# progressled.net
KiCad netlist of a schematic drawn in Altium Designer
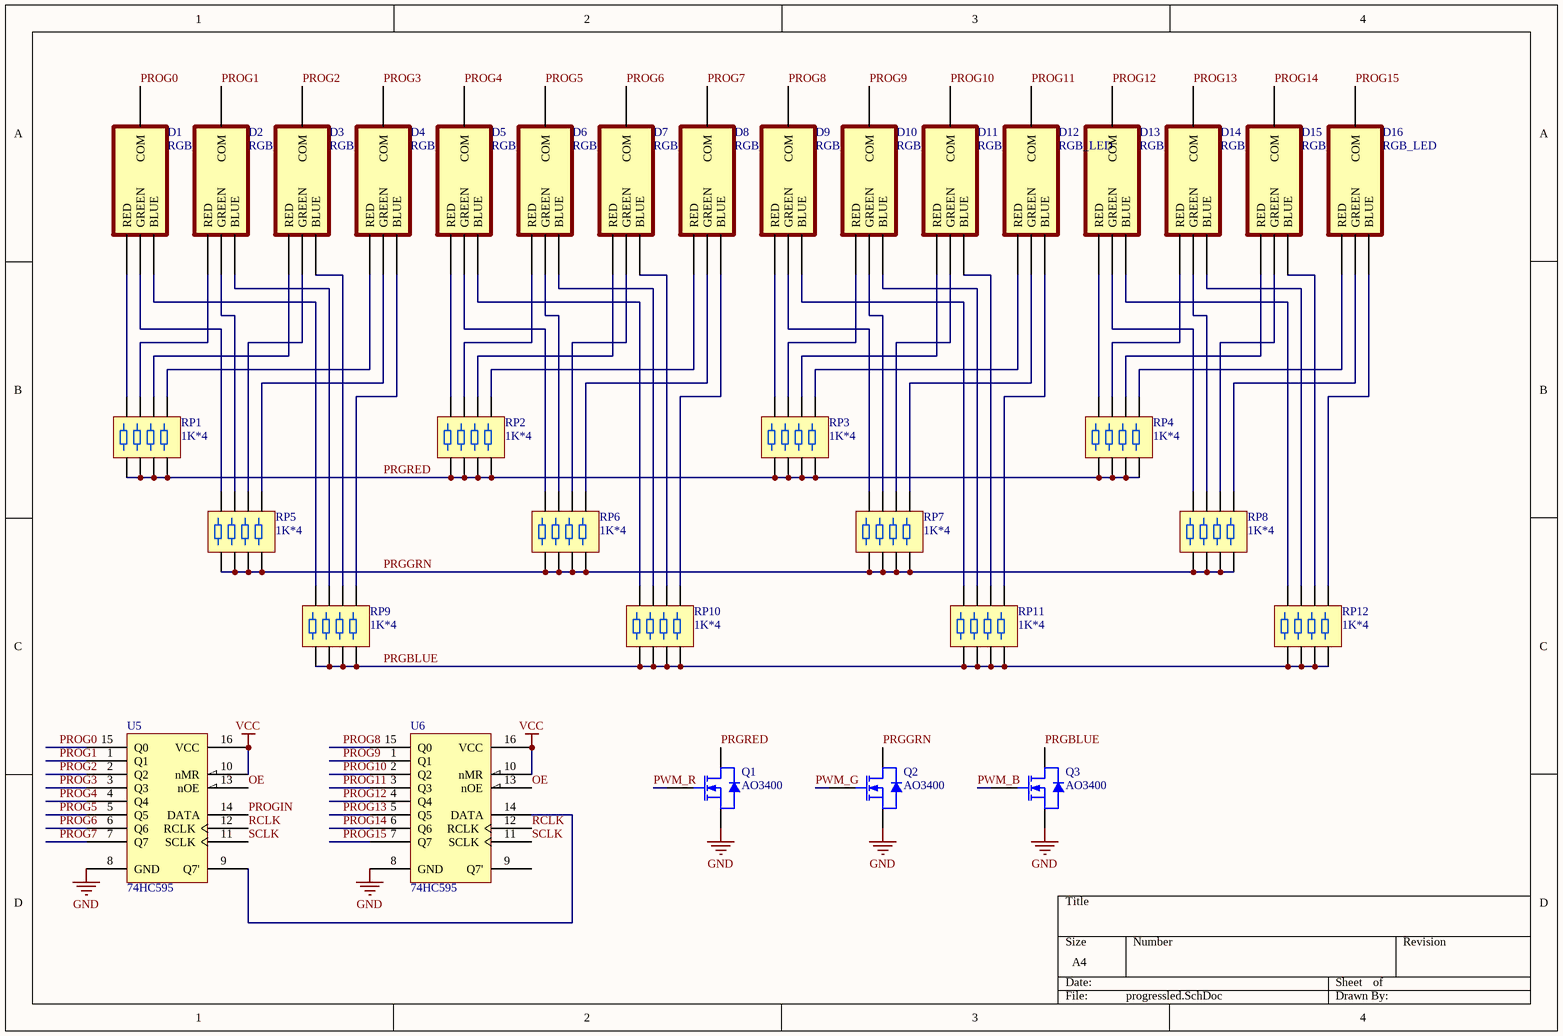
[diagram p0: progressled.SchDoc]

(export (version "E")
  (design (tool "Eeschema 10.0.6"))
  (components
    (comp (ref "D1")
      (value "RGB_LED")
      (footprint "0805_RGB")
      (libsource (lib "ntw_oldschlib") (part "RGBLED"))
    )
    (comp (ref "D2")
      (value "RGB_LED")
      (footprint "0805_RGB")
      (libsource (lib "ntw_oldschlib") (part "RGBLED"))
    )
    (comp (ref "D3")
      (value "RGB_LED")
      (footprint "0805_RGB")
      (libsource (lib "ntw_oldschlib") (part "RGBLED"))
    )
    (comp (ref "D4")
      (value "RGB_LED")
      (footprint "0805_RGB")
      (libsource (lib "ntw_oldschlib") (part "RGBLED"))
    )
    (comp (ref "D5")
      (value "RGB_LED")
      (footprint "0805_RGB")
      (libsource (lib "ntw_oldschlib") (part "RGBLED"))
    )
    (comp (ref "D6")
      (value "RGB_LED")
      (footprint "0805_RGB")
      (libsource (lib "ntw_oldschlib") (part "RGBLED"))
    )
    (comp (ref "D7")
      (value "RGB_LED")
      (footprint "0805_RGB")
      (libsource (lib "ntw_oldschlib") (part "RGBLED"))
    )
    (comp (ref "D8")
      (value "RGB_LED")
      (footprint "0805_RGB")
      (libsource (lib "ntw_oldschlib") (part "RGBLED"))
    )
    (comp (ref "D9")
      (value "RGB_LED")
      (footprint "0805_RGB")
      (libsource (lib "ntw_oldschlib") (part "RGBLED"))
    )
    (comp (ref "D10")
      (value "RGB_LED")
      (footprint "0805_RGB")
      (libsource (lib "ntw_oldschlib") (part "RGBLED"))
    )
    (comp (ref "D11")
      (value "RGB_LED")
      (footprint "0805_RGB")
      (libsource (lib "ntw_oldschlib") (part "RGBLED"))
    )
    (comp (ref "D12")
      (value "RGB_LED")
      (footprint "0805_RGB")
      (libsource (lib "ntw_oldschlib") (part "RGBLED"))
    )
    (comp (ref "D13")
      (value "RGB_LED")
      (footprint "0805_RGB")
      (libsource (lib "ntw_oldschlib") (part "RGBLED"))
    )
    (comp (ref "D14")
      (value "RGB_LED")
      (footprint "0805_RGB")
      (libsource (lib "ntw_oldschlib") (part "RGBLED"))
    )
    (comp (ref "D15")
      (value "RGB_LED")
      (footprint "0805_RGB")
      (libsource (lib "ntw_oldschlib") (part "RGBLED"))
    )
    (comp (ref "D16")
      (value "RGB_LED")
      (footprint "0805_RGB")
      (libsource (lib "ntw_oldschlib") (part "RGBLED"))
    )
    (comp (ref "Q1")
      (value "AO3400")
      (footprint "SOT-23")
      (description "N-Channel MOSFET")
      (fields (field (name "PUBLISHER") "Altium Limited"))
      (libsource (lib "ntw_oldschlib") (part "AO3400"))
    )
    (comp (ref "Q2")
      (value "AO3400")
      (footprint "SOT-23")
      (description "N-Channel MOSFET")
      (fields (field (name "PUBLISHER") "Altium Limited"))
      (libsource (lib "ntw_oldschlib") (part "AO3400"))
    )
    (comp (ref "Q3")
      (value "AO3400")
      (footprint "SOT-23")
      (description "N-Channel MOSFET")
      (fields (field (name "PUBLISHER") "Altium Limited"))
      (libsource (lib "ntw_oldschlib") (part "AO3400"))
    )
    (comp (ref "RP1") (value "1K*4") (footprint "0603x4") (libsource (lib "ntw_oldschlib") (part "RPack_4")))
    (comp (ref "RP2") (value "1K*4") (footprint "0603x4") (libsource (lib "ntw_oldschlib") (part "RPack_4")))
    (comp (ref "RP3") (value "1K*4") (footprint "0603x4") (libsource (lib "ntw_oldschlib") (part "RPack_4")))
    (comp (ref "RP4") (value "1K*4") (footprint "0603x4") (libsource (lib "ntw_oldschlib") (part "RPack_4")))
    (comp (ref "RP5") (value "1K*4") (footprint "0603x4") (libsource (lib "ntw_oldschlib") (part "RPack_4")))
    (comp (ref "RP6") (value "1K*4") (footprint "0603x4") (libsource (lib "ntw_oldschlib") (part "RPack_4")))
    (comp (ref "RP7") (value "1K*4") (footprint "0603x4") (libsource (lib "ntw_oldschlib") (part "RPack_4")))
    (comp (ref "RP8") (value "1K*4") (footprint "0603x4") (libsource (lib "ntw_oldschlib") (part "RPack_4")))
    (comp (ref "RP9") (value "1K*4") (footprint "0603x4") (libsource (lib "ntw_oldschlib") (part "RPack_4")))
    (comp (ref "RP10") (value "1K*4") (footprint "0603x4") (libsource (lib "ntw_oldschlib") (part "RPack_4")))
    (comp (ref "RP11") (value "1K*4") (footprint "0603x4") (libsource (lib "ntw_oldschlib") (part "RPack_4")))
    (comp (ref "RP12") (value "1K*4") (footprint "0603x4") (libsource (lib "ntw_oldschlib") (part "RPack_4")))
    (comp (ref "U5")
      (value "74HC595")
      (footprint "TSSOP16")
      (description "8-bit serial-in, serial or parallel-out shift register with output latches; 3-state")
      (libsource (lib "ntw_oldschlib") (part "74HC595"))
    )
    (comp (ref "U6")
      (value "74HC595")
      (footprint "TSSOP16")
      (description "8-bit serial-in, serial or parallel-out shift register with output latches; 3-state")
      (libsource (lib "ntw_oldschlib") (part "74HC595"))
    )
  )
  (nets
    (net (code "1") (name "/OE") (class "Default")
      (node (ref "U5") (pin "13") (pinfunction "nOE_13") (pintype "passive"))
      (node (ref "U6") (pin "13") (pinfunction "nOE_13") (pintype "passive"))
    )
    (net (code "2") (name "/PRGBLUE") (class "Default")
      (node (ref "Q3") (pin "3") (pinfunction "D_3") (pintype "passive"))
      (node (ref "RP10") (pin "1") (pinfunction "1_1") (pintype "passive"))
      (node (ref "RP10") (pin "2") (pinfunction "2_2") (pintype "passive"))
      (node (ref "RP10") (pin "3") (pinfunction "3_3") (pintype "passive"))
      (node (ref "RP10") (pin "4") (pinfunction "4_4") (pintype "passive"))
      (node (ref "RP11") (pin "1") (pinfunction "1_1") (pintype "passive"))
      (node (ref "RP11") (pin "2") (pinfunction "2_2") (pintype "passive"))
      (node (ref "RP11") (pin "3") (pinfunction "3_3") (pintype "passive"))
      (node (ref "RP11") (pin "4") (pinfunction "4_4") (pintype "passive"))
      (node (ref "RP12") (pin "1") (pinfunction "1_1") (pintype "passive"))
      (node (ref "RP12") (pin "2") (pinfunction "2_2") (pintype "passive"))
      (node (ref "RP12") (pin "3") (pinfunction "3_3") (pintype "passive"))
      (node (ref "RP12") (pin "4") (pinfunction "4_4") (pintype "passive"))
      (node (ref "RP9") (pin "1") (pinfunction "1_1") (pintype "passive"))
      (node (ref "RP9") (pin "2") (pinfunction "2_2") (pintype "passive"))
      (node (ref "RP9") (pin "3") (pinfunction "3_3") (pintype "passive"))
      (node (ref "RP9") (pin "4") (pinfunction "4_4") (pintype "passive"))
    )
    (net (code "3") (name "/PRGGRN") (class "Default")
      (node (ref "Q2") (pin "3") (pinfunction "D_3") (pintype "passive"))
      (node (ref "RP5") (pin "1") (pinfunction "1_1") (pintype "passive"))
      (node (ref "RP5") (pin "2") (pinfunction "2_2") (pintype "passive"))
      (node (ref "RP5") (pin "3") (pinfunction "3_3") (pintype "passive"))
      (node (ref "RP5") (pin "4") (pinfunction "4_4") (pintype "passive"))
      (node (ref "RP6") (pin "1") (pinfunction "1_1") (pintype "passive"))
      (node (ref "RP6") (pin "2") (pinfunction "2_2") (pintype "passive"))
      (node (ref "RP6") (pin "3") (pinfunction "3_3") (pintype "passive"))
      (node (ref "RP6") (pin "4") (pinfunction "4_4") (pintype "passive"))
      (node (ref "RP7") (pin "1") (pinfunction "1_1") (pintype "passive"))
      (node (ref "RP7") (pin "2") (pinfunction "2_2") (pintype "passive"))
      (node (ref "RP7") (pin "3") (pinfunction "3_3") (pintype "passive"))
      (node (ref "RP7") (pin "4") (pinfunction "4_4") (pintype "passive"))
      (node (ref "RP8") (pin "1") (pinfunction "1_1") (pintype "passive"))
      (node (ref "RP8") (pin "2") (pinfunction "2_2") (pintype "passive"))
      (node (ref "RP8") (pin "3") (pinfunction "3_3") (pintype "passive"))
      (node (ref "RP8") (pin "4") (pinfunction "4_4") (pintype "passive"))
    )
    (net (code "4") (name "/PRGRED") (class "Default")
      (node (ref "Q1") (pin "3") (pinfunction "D_3") (pintype "passive"))
      (node (ref "RP1") (pin "1") (pinfunction "1_1") (pintype "passive"))
      (node (ref "RP1") (pin "2") (pinfunction "2_2") (pintype "passive"))
      (node (ref "RP1") (pin "3") (pinfunction "3_3") (pintype "passive"))
      (node (ref "RP1") (pin "4") (pinfunction "4_4") (pintype "passive"))
      (node (ref "RP2") (pin "1") (pinfunction "1_1") (pintype "passive"))
      (node (ref "RP2") (pin "2") (pinfunction "2_2") (pintype "passive"))
      (node (ref "RP2") (pin "3") (pinfunction "3_3") (pintype "passive"))
      (node (ref "RP2") (pin "4") (pinfunction "4_4") (pintype "passive"))
      (node (ref "RP3") (pin "1") (pinfunction "1_1") (pintype "passive"))
      (node (ref "RP3") (pin "2") (pinfunction "2_2") (pintype "passive"))
      (node (ref "RP3") (pin "3") (pinfunction "3_3") (pintype "passive"))
      (node (ref "RP3") (pin "4") (pinfunction "4_4") (pintype "passive"))
      (node (ref "RP4") (pin "1") (pinfunction "1_1") (pintype "passive"))
      (node (ref "RP4") (pin "2") (pinfunction "2_2") (pintype "passive"))
      (node (ref "RP4") (pin "3") (pinfunction "3_3") (pintype "passive"))
      (node (ref "RP4") (pin "4") (pinfunction "4_4") (pintype "passive"))
    )
    (net (code "5") (name "/PROG0") (class "Default")
      (node (ref "D1") (pin "COM") (pinfunction "COM_COM") (pintype "passive"))
      (node (ref "U5") (pin "15") (pinfunction "Q0_15") (pintype "passive"))
    )
    (net (code "6") (name "/PROG1") (class "Default")
      (node (ref "D2") (pin "COM") (pinfunction "COM_COM") (pintype "passive"))
      (node (ref "U5") (pin "1") (pinfunction "Q1_1") (pintype "passive"))
    )
    (net (code "7") (name "/PROG2") (class "Default")
      (node (ref "D3") (pin "COM") (pinfunction "COM_COM") (pintype "passive"))
      (node (ref "U5") (pin "2") (pinfunction "Q2_2") (pintype "passive"))
    )
    (net (code "8") (name "/PROG3") (class "Default")
      (node (ref "D4") (pin "COM") (pinfunction "COM_COM") (pintype "passive"))
      (node (ref "U5") (pin "3") (pinfunction "Q3_3") (pintype "passive"))
    )
    (net (code "9") (name "/PROG4") (class "Default")
      (node (ref "D5") (pin "COM") (pinfunction "COM_COM") (pintype "passive"))
      (node (ref "U5") (pin "4") (pinfunction "Q4_4") (pintype "passive"))
    )
    (net (code "10") (name "/PROG5") (class "Default")
      (node (ref "D6") (pin "COM") (pinfunction "COM_COM") (pintype "passive"))
      (node (ref "U5") (pin "5") (pinfunction "Q5_5") (pintype "passive"))
    )
    (net (code "11") (name "/PROG6") (class "Default")
      (node (ref "D7") (pin "COM") (pinfunction "COM_COM") (pintype "passive"))
      (node (ref "U5") (pin "6") (pinfunction "Q6_6") (pintype "passive"))
    )
    (net (code "12") (name "/PROG7") (class "Default")
      (node (ref "D8") (pin "COM") (pinfunction "COM_COM") (pintype "passive"))
      (node (ref "U5") (pin "7") (pinfunction "Q7_7") (pintype "passive"))
    )
    (net (code "13") (name "/PROG8") (class "Default")
      (node (ref "D9") (pin "COM") (pinfunction "COM_COM") (pintype "passive"))
      (node (ref "U6") (pin "15") (pinfunction "Q0_15") (pintype "passive"))
    )
    (net (code "14") (name "/PROG9") (class "Default")
      (node (ref "D10") (pin "COM") (pinfunction "COM_COM") (pintype "passive"))
      (node (ref "U6") (pin "1") (pinfunction "Q1_1") (pintype "passive"))
    )
    (net (code "15") (name "/PROG10") (class "Default")
      (node (ref "D11") (pin "COM") (pinfunction "COM_COM") (pintype "passive"))
      (node (ref "U6") (pin "2") (pinfunction "Q2_2") (pintype "passive"))
    )
    (net (code "16") (name "/PROG11") (class "Default")
      (node (ref "D12") (pin "COM") (pinfunction "COM_COM") (pintype "passive"))
      (node (ref "U6") (pin "3") (pinfunction "Q3_3") (pintype "passive"))
    )
    (net (code "17") (name "/PROG12") (class "Default")
      (node (ref "D13") (pin "COM") (pinfunction "COM_COM") (pintype "passive"))
      (node (ref "U6") (pin "4") (pinfunction "Q4_4") (pintype "passive"))
    )
    (net (code "18") (name "/PROG13") (class "Default")
      (node (ref "D14") (pin "COM") (pinfunction "COM_COM") (pintype "passive"))
      (node (ref "U6") (pin "5") (pinfunction "Q5_5") (pintype "passive"))
    )
    (net (code "19") (name "/PROG14") (class "Default")
      (node (ref "D15") (pin "COM") (pinfunction "COM_COM") (pintype "passive"))
      (node (ref "U6") (pin "6") (pinfunction "Q6_6") (pintype "passive"))
    )
    (net (code "20") (name "/PROG15") (class "Default")
      (node (ref "D16") (pin "COM") (pinfunction "COM_COM") (pintype "passive"))
      (node (ref "U6") (pin "7") (pinfunction "Q7_7") (pintype "passive"))
    )
    (net (code "21") (name "/PROGIN") (class "Default")
      (node (ref "U5") (pin "14") (pinfunction "DATA_14") (pintype "passive"))
    )
    (net (code "22") (name "/PWM_B") (class "Default")
      (node (ref "Q3") (pin "1") (pinfunction "G_1") (pintype "passive"))
    )
    (net (code "23") (name "/PWM_G") (class "Default")
      (node (ref "Q2") (pin "1") (pinfunction "G_1") (pintype "passive"))
    )
    (net (code "24") (name "/PWM_R") (class "Default")
      (node (ref "Q1") (pin "1") (pinfunction "G_1") (pintype "passive"))
    )
    (net (code "25") (name "/RCLK") (class "Default")
      (node (ref "U5") (pin "12") (pinfunction "RCLK_12") (pintype "passive"))
      (node (ref "U6") (pin "12") (pinfunction "RCLK_12") (pintype "passive"))
    )
    (net (code "26") (name "/SCLK") (class "Default")
      (node (ref "U5") (pin "11") (pinfunction "SCLK_11") (pintype "passive"))
      (node (ref "U6") (pin "11") (pinfunction "SCLK_11") (pintype "passive"))
    )
    (net (code "27") (name "GND") (class "Default")
      (node (ref "Q1") (pin "2") (pinfunction "S_2") (pintype "passive"))
      (node (ref "Q2") (pin "2") (pinfunction "S_2") (pintype "passive"))
      (node (ref "Q3") (pin "2") (pinfunction "S_2") (pintype "passive"))
      (node (ref "U5") (pin "8") (pinfunction "GND_8") (pintype "passive"))
      (node (ref "U6") (pin "8") (pinfunction "GND_8") (pintype "passive"))
    )
    (net (code "28") (name "Net-(D1-BLUE)") (class "Default")
      (node (ref "D1") (pin "B") (pinfunction "BLUE_B") (pintype "passive"))
      (node (ref "RP9") (pin "8") (pinfunction "8_8") (pintype "passive"))
    )
    (net (code "29") (name "Net-(D1-GREEN)") (class "Default")
      (node (ref "D1") (pin "G") (pinfunction "GREEN_G") (pintype "passive"))
      (node (ref "RP5") (pin "8") (pinfunction "8_8") (pintype "passive"))
    )
    (net (code "30") (name "Net-(D1-RED)") (class "Default")
      (node (ref "D1") (pin "R") (pinfunction "RED_R") (pintype "passive"))
      (node (ref "RP1") (pin "8") (pinfunction "8_8") (pintype "passive"))
    )
    (net (code "31") (name "Net-(D2-BLUE)") (class "Default")
      (node (ref "D2") (pin "B") (pinfunction "BLUE_B") (pintype "passive"))
      (node (ref "RP9") (pin "7") (pinfunction "7_7") (pintype "passive"))
    )
    (net (code "32") (name "Net-(D2-GREEN)") (class "Default")
      (node (ref "D2") (pin "G") (pinfunction "GREEN_G") (pintype "passive"))
      (node (ref "RP5") (pin "7") (pinfunction "7_7") (pintype "passive"))
    )
    (net (code "33") (name "Net-(D2-RED)") (class "Default")
      (node (ref "D2") (pin "R") (pinfunction "RED_R") (pintype "passive"))
      (node (ref "RP1") (pin "7") (pinfunction "7_7") (pintype "passive"))
    )
    (net (code "34") (name "Net-(D3-BLUE)") (class "Default")
      (node (ref "D3") (pin "B") (pinfunction "BLUE_B") (pintype "passive"))
      (node (ref "RP9") (pin "6") (pinfunction "6_6") (pintype "passive"))
    )
    (net (code "35") (name "Net-(D3-GREEN)") (class "Default")
      (node (ref "D3") (pin "G") (pinfunction "GREEN_G") (pintype "passive"))
      (node (ref "RP5") (pin "6") (pinfunction "6_6") (pintype "passive"))
    )
    (net (code "36") (name "Net-(D3-RED)") (class "Default")
      (node (ref "D3") (pin "R") (pinfunction "RED_R") (pintype "passive"))
      (node (ref "RP1") (pin "6") (pinfunction "6_6") (pintype "passive"))
    )
    (net (code "37") (name "Net-(D4-BLUE)") (class "Default")
      (node (ref "D4") (pin "B") (pinfunction "BLUE_B") (pintype "passive"))
      (node (ref "RP9") (pin "5") (pinfunction "5_5") (pintype "passive"))
    )
    (net (code "38") (name "Net-(D4-GREEN)") (class "Default")
      (node (ref "D4") (pin "G") (pinfunction "GREEN_G") (pintype "passive"))
      (node (ref "RP5") (pin "5") (pinfunction "5_5") (pintype "passive"))
    )
    (net (code "39") (name "Net-(D4-RED)") (class "Default")
      (node (ref "D4") (pin "R") (pinfunction "RED_R") (pintype "passive"))
      (node (ref "RP1") (pin "5") (pinfunction "5_5") (pintype "passive"))
    )
    (net (code "40") (name "Net-(D5-BLUE)") (class "Default")
      (node (ref "D5") (pin "B") (pinfunction "BLUE_B") (pintype "passive"))
      (node (ref "RP10") (pin "8") (pinfunction "8_8") (pintype "passive"))
    )
    (net (code "41") (name "Net-(D5-GREEN)") (class "Default")
      (node (ref "D5") (pin "G") (pinfunction "GREEN_G") (pintype "passive"))
      (node (ref "RP6") (pin "8") (pinfunction "8_8") (pintype "passive"))
    )
    (net (code "42") (name "Net-(D5-RED)") (class "Default")
      (node (ref "D5") (pin "R") (pinfunction "RED_R") (pintype "passive"))
      (node (ref "RP2") (pin "8") (pinfunction "8_8") (pintype "passive"))
    )
    (net (code "43") (name "Net-(D6-BLUE)") (class "Default")
      (node (ref "D6") (pin "B") (pinfunction "BLUE_B") (pintype "passive"))
      (node (ref "RP10") (pin "7") (pinfunction "7_7") (pintype "passive"))
    )
    (net (code "44") (name "Net-(D6-GREEN)") (class "Default")
      (node (ref "D6") (pin "G") (pinfunction "GREEN_G") (pintype "passive"))
      (node (ref "RP6") (pin "7") (pinfunction "7_7") (pintype "passive"))
    )
    (net (code "45") (name "Net-(D6-RED)") (class "Default")
      (node (ref "D6") (pin "R") (pinfunction "RED_R") (pintype "passive"))
      (node (ref "RP2") (pin "7") (pinfunction "7_7") (pintype "passive"))
    )
    (net (code "46") (name "Net-(D7-BLUE)") (class "Default")
      (node (ref "D7") (pin "B") (pinfunction "BLUE_B") (pintype "passive"))
      (node (ref "RP10") (pin "6") (pinfunction "6_6") (pintype "passive"))
    )
    (net (code "47") (name "Net-(D7-GREEN)") (class "Default")
      (node (ref "D7") (pin "G") (pinfunction "GREEN_G") (pintype "passive"))
      (node (ref "RP6") (pin "6") (pinfunction "6_6") (pintype "passive"))
    )
    (net (code "48") (name "Net-(D7-RED)") (class "Default")
      (node (ref "D7") (pin "R") (pinfunction "RED_R") (pintype "passive"))
      (node (ref "RP2") (pin "6") (pinfunction "6_6") (pintype "passive"))
    )
    (net (code "49") (name "Net-(D8-BLUE)") (class "Default")
      (node (ref "D8") (pin "B") (pinfunction "BLUE_B") (pintype "passive"))
      (node (ref "RP10") (pin "5") (pinfunction "5_5") (pintype "passive"))
    )
    (net (code "50") (name "Net-(D8-GREEN)") (class "Default")
      (node (ref "D8") (pin "G") (pinfunction "GREEN_G") (pintype "passive"))
      (node (ref "RP6") (pin "5") (pinfunction "5_5") (pintype "passive"))
    )
    (net (code "51") (name "Net-(D8-RED)") (class "Default")
      (node (ref "D8") (pin "R") (pinfunction "RED_R") (pintype "passive"))
      (node (ref "RP2") (pin "5") (pinfunction "5_5") (pintype "passive"))
    )
    (net (code "52") (name "Net-(D9-BLUE)") (class "Default")
      (node (ref "D9") (pin "B") (pinfunction "BLUE_B") (pintype "passive"))
      (node (ref "RP11") (pin "8") (pinfunction "8_8") (pintype "passive"))
    )
    (net (code "53") (name "Net-(D9-GREEN)") (class "Default")
      (node (ref "D9") (pin "G") (pinfunction "GREEN_G") (pintype "passive"))
      (node (ref "RP7") (pin "8") (pinfunction "8_8") (pintype "passive"))
    )
    (net (code "54") (name "Net-(D9-RED)") (class "Default")
      (node (ref "D9") (pin "R") (pinfunction "RED_R") (pintype "passive"))
      (node (ref "RP3") (pin "8") (pinfunction "8_8") (pintype "passive"))
    )
    (net (code "55") (name "Net-(D10-BLUE)") (class "Default")
      (node (ref "D10") (pin "B") (pinfunction "BLUE_B") (pintype "passive"))
      (node (ref "RP11") (pin "7") (pinfunction "7_7") (pintype "passive"))
    )
    (net (code "56") (name "Net-(D10-GREEN)") (class "Default")
      (node (ref "D10") (pin "G") (pinfunction "GREEN_G") (pintype "passive"))
      (node (ref "RP7") (pin "7") (pinfunction "7_7") (pintype "passive"))
    )
    (net (code "57") (name "Net-(D10-RED)") (class "Default")
      (node (ref "D10") (pin "R") (pinfunction "RED_R") (pintype "passive"))
      (node (ref "RP3") (pin "7") (pinfunction "7_7") (pintype "passive"))
    )
    (net (code "58") (name "Net-(D11-BLUE)") (class "Default")
      (node (ref "D11") (pin "B") (pinfunction "BLUE_B") (pintype "passive"))
      (node (ref "RP11") (pin "6") (pinfunction "6_6") (pintype "passive"))
    )
    (net (code "59") (name "Net-(D11-GREEN)") (class "Default")
      (node (ref "D11") (pin "G") (pinfunction "GREEN_G") (pintype "passive"))
      (node (ref "RP7") (pin "6") (pinfunction "6_6") (pintype "passive"))
    )
    (net (code "60") (name "Net-(D11-RED)") (class "Default")
      (node (ref "D11") (pin "R") (pinfunction "RED_R") (pintype "passive"))
      (node (ref "RP3") (pin "6") (pinfunction "6_6") (pintype "passive"))
    )
    (net (code "61") (name "Net-(D12-BLUE)") (class "Default")
      (node (ref "D12") (pin "B") (pinfunction "BLUE_B") (pintype "passive"))
      (node (ref "RP11") (pin "5") (pinfunction "5_5") (pintype "passive"))
    )
    (net (code "62") (name "Net-(D12-GREEN)") (class "Default")
      (node (ref "D12") (pin "G") (pinfunction "GREEN_G") (pintype "passive"))
      (node (ref "RP7") (pin "5") (pinfunction "5_5") (pintype "passive"))
    )
    (net (code "63") (name "Net-(D12-RED)") (class "Default")
      (node (ref "D12") (pin "R") (pinfunction "RED_R") (pintype "passive"))
      (node (ref "RP3") (pin "5") (pinfunction "5_5") (pintype "passive"))
    )
    (net (code "64") (name "Net-(D13-BLUE)") (class "Default")
      (node (ref "D13") (pin "B") (pinfunction "BLUE_B") (pintype "passive"))
      (node (ref "RP12") (pin "8") (pinfunction "8_8") (pintype "passive"))
    )
    (net (code "65") (name "Net-(D13-GREEN)") (class "Default")
      (node (ref "D13") (pin "G") (pinfunction "GREEN_G") (pintype "passive"))
      (node (ref "RP8") (pin "8") (pinfunction "8_8") (pintype "passive"))
    )
    (net (code "66") (name "Net-(D13-RED)") (class "Default")
      (node (ref "D13") (pin "R") (pinfunction "RED_R") (pintype "passive"))
      (node (ref "RP4") (pin "8") (pinfunction "8_8") (pintype "passive"))
    )
    (net (code "67") (name "Net-(D14-BLUE)") (class "Default")
      (node (ref "D14") (pin "B") (pinfunction "BLUE_B") (pintype "passive"))
      (node (ref "RP12") (pin "7") (pinfunction "7_7") (pintype "passive"))
    )
    (net (code "68") (name "Net-(D14-GREEN)") (class "Default")
      (node (ref "D14") (pin "G") (pinfunction "GREEN_G") (pintype "passive"))
      (node (ref "RP8") (pin "7") (pinfunction "7_7") (pintype "passive"))
    )
    (net (code "69") (name "Net-(D14-RED)") (class "Default")
      (node (ref "D14") (pin "R") (pinfunction "RED_R") (pintype "passive"))
      (node (ref "RP4") (pin "7") (pinfunction "7_7") (pintype "passive"))
    )
    (net (code "70") (name "Net-(D15-BLUE)") (class "Default")
      (node (ref "D15") (pin "B") (pinfunction "BLUE_B") (pintype "passive"))
      (node (ref "RP12") (pin "6") (pinfunction "6_6") (pintype "passive"))
    )
    (net (code "71") (name "Net-(D15-GREEN)") (class "Default")
      (node (ref "D15") (pin "G") (pinfunction "GREEN_G") (pintype "passive"))
      (node (ref "RP8") (pin "6") (pinfunction "6_6") (pintype "passive"))
    )
    (net (code "72") (name "Net-(D15-RED)") (class "Default")
      (node (ref "D15") (pin "R") (pinfunction "RED_R") (pintype "passive"))
      (node (ref "RP4") (pin "6") (pinfunction "6_6") (pintype "passive"))
    )
    (net (code "73") (name "Net-(D16-BLUE)") (class "Default")
      (node (ref "D16") (pin "B") (pinfunction "BLUE_B") (pintype "passive"))
      (node (ref "RP12") (pin "5") (pinfunction "5_5") (pintype "passive"))
    )
    (net (code "74") (name "Net-(D16-GREEN)") (class "Default")
      (node (ref "D16") (pin "G") (pinfunction "GREEN_G") (pintype "passive"))
      (node (ref "RP8") (pin "5") (pinfunction "5_5") (pintype "passive"))
    )
    (net (code "75") (name "Net-(D16-RED)") (class "Default")
      (node (ref "D16") (pin "R") (pinfunction "RED_R") (pintype "passive"))
      (node (ref "RP4") (pin "5") (pinfunction "5_5") (pintype "passive"))
    )
    (net (code "76") (name "Net-(U5-Q7')") (class "Default")
      (node (ref "U5") (pin "9") (pinfunction "Q7'_9") (pintype "passive"))
      (node (ref "U6") (pin "14") (pinfunction "DATA_14") (pintype "passive"))
    )
    (net (code "77") (name "VCC") (class "Default")
      (node (ref "U5") (pin "10") (pinfunction "nMR_10") (pintype "passive"))
      (node (ref "U5") (pin "16") (pinfunction "VCC_16") (pintype "passive"))
      (node (ref "U6") (pin "10") (pinfunction "nMR_10") (pintype "passive"))
      (node (ref "U6") (pin "16") (pinfunction "VCC_16") (pintype "passive"))
    )
    (net (code "78") (name "unconnected-(U6-Q7'-Pad9)") (class "Default")
      (node (ref "U6") (pin "9") (pinfunction "Q7'_9") (pintype "passive"))
    )
  )
)
